# ABA-52563-SCH.net
KiCad netlist of a schematic drawn in Altium Designer
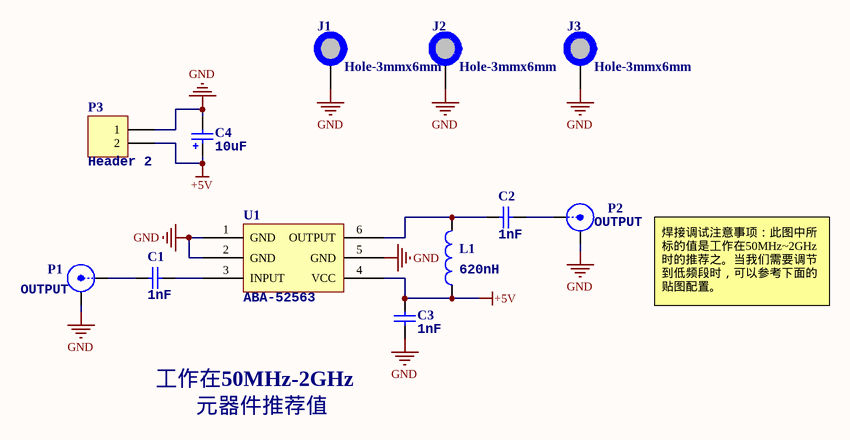
[diagram p0: ABA-52563-SCH.SchDoc]

(export (version "E")
  (design (tool "Eeschema 10.0.6"))
  (components
    (comp (ref "C1")
      (value "1nF")
      (footprint "0603C")
      (description "CAP CER 10000PF 100V X7R 0603")
      (fields
        (field (name "MANUFACTURER") "TDK Corporation")
        (field (name "MANUFACTURER PART NUMBER") "C1608X7R2A103K080AA")
      )
      (libsource (lib "Desiger_Schlib") (part "Cap1"))
    )
    (comp (ref "C2")
      (value "1nF")
      (footprint "0603C")
      (description "CAP CER 10000PF 100V X7R 0603")
      (fields
        (field (name "MANUFACTURER") "TDK Corporation")
        (field (name "MANUFACTURER PART NUMBER") "C1608X7R2A103K080AA")
      )
      (libsource (lib "Desiger_Schlib") (part "Cap1"))
    )
    (comp (ref "C3")
      (value "1nF")
      (footprint "0603C")
      (description "CAP CER 10000PF 100V X7R 0603")
      (fields
        (field (name "MANUFACTURER") "TDK Corporation")
        (field (name "MANUFACTURER PART NUMBER") "C1608X7R2A103K080AA")
      )
      (libsource (lib "Desiger_Schlib") (part "Cap1"))
    )
    (comp (ref "C4")
      (value "10uF")
      (footprint "1206T")
      (description "CAP TANT 10UF 10V 10% 1206")
      (fields
        (field (name "MANUFACTURER") "KEMET")
        (field (name "MANUFACTURER PART NUMBER") "T491A106K010AT7280")
      )
      (libsource (lib "Desiger_Schlib") (part "Cap2"))
    )
    (comp (ref "J1")
      (value "Hole-3mmx6mm")
      (footprint "Hole")
      (libsource (lib "Desiger_Schlib") (part "HOLED"))
    )
    (comp (ref "J2")
      (value "Hole-3mmx6mm")
      (footprint "Hole")
      (libsource (lib "Desiger_Schlib") (part "HOLED"))
    )
    (comp (ref "J3")
      (value "Hole-3mmx6mm")
      (footprint "Hole")
      (libsource (lib "Desiger_Schlib") (part "HOLED"))
    )
    (comp (ref "L1")
      (value "620nH")
      (footprint "0603L")
      (description "FIXED IND 240NH 4.4A 22MOHM SMD")
      (fields
        (field (name "MANUFACTURER") "Samsung Electro-Mechanics")
        (field (name "MANUFACTURER PART NUMBER") "CIGT201210UHR24MNE")
      )
      (libsource (lib "Desiger_Schlib") (part "Inductors"))
    )
    (comp (ref "P1")
      (value "OUTPUT")
      (footprint "SMA-SMD")
      (description "BNC Elbow Connector")
      (fields (field (name "PUBLISHER") "Altium Limited"))
      (libsource (lib "Miscellaneous Connectors") (part "BNC"))
    )
    (comp (ref "P2")
      (value "OUTPUT")
      (footprint "SMA-SMD")
      (description "BNC Elbow Connector")
      (fields (field (name "PUBLISHER") "Altium Limited"))
      (libsource (lib "Miscellaneous Connectors") (part "BNC"))
    )
    (comp (ref "P3")
      (value "Header 2")
      (footprint "KF2EDG_3R81_2P")
      (description "Header, 2-Pin")
      (fields (field (name "PUBLISHER") "Altium Limited"))
      (libsource (lib "Miscellaneous Connectors") (part "Header 2"))
    )
    (comp (ref "U1")
      (value "ABA-52563")
      (footprint "SOT23-6")
      (description "Agilent ABA-52563  3.5 GHz Broadband Silicon  RFIC Amplifier")
      (libsource (lib "Desiger_Schlib") (part "ABA-52563"))
    )
  )
  (nets
    (net (code "1") (name "+5V") (class "Default")
      (node (ref "C3") (pin "1") (pinfunction "1_1") (pintype "passive"))
      (node (ref "C4") (pin "1") (pinfunction "+_1") (pintype "passive"))
      (node (ref "L1") (pin "1") (pinfunction "1_1") (pintype "passive"))
      (node (ref "P3") (pin "2") (pinfunction "2_2") (pintype "passive"))
      (node (ref "U1") (pin "4") (pinfunction "VCC_4") (pintype "passive"))
    )
    (net (code "2") (name "GND") (class "Default")
      (node (ref "C3") (pin "2") (pinfunction "2_2") (pintype "passive"))
      (node (ref "C4") (pin "2") (pinfunction "-_2") (pintype "passive"))
      (node (ref "J1") (pin "0") (pinfunction "0_0") (pintype "passive"))
      (node (ref "J2") (pin "0") (pinfunction "0_0") (pintype "passive"))
      (node (ref "J3") (pin "0") (pinfunction "0_0") (pintype "passive"))
      (node (ref "P1") (pin "2") (pinfunction "Y_2") (pintype "passive"))
      (node (ref "P2") (pin "2") (pinfunction "Y_2") (pintype "passive"))
      (node (ref "P3") (pin "1") (pinfunction "1_1") (pintype "passive"))
      (node (ref "U1") (pin "1") (pinfunction "GND_1") (pintype "passive"))
      (node (ref "U1") (pin "2") (pinfunction "GND_2") (pintype "passive"))
      (node (ref "U1") (pin "5") (pinfunction "GND_5") (pintype "passive"))
    )
    (net (code "3") (name "Net-(P1-X)") (class "Default")
      (node (ref "C1") (pin "1") (pinfunction "1_1") (pintype "passive"))
      (node (ref "P1") (pin "1") (pinfunction "X_1") (pintype "passive"))
    )
    (net (code "4") (name "Net-(P2-X)") (class "Default")
      (node (ref "C2") (pin "2") (pinfunction "2_2") (pintype "passive"))
      (node (ref "P2") (pin "1") (pinfunction "X_1") (pintype "passive"))
    )
    (net (code "5") (name "Net-(U1-INPUT)") (class "Default")
      (node (ref "C1") (pin "2") (pinfunction "2_2") (pintype "passive"))
      (node (ref "U1") (pin "3") (pinfunction "INPUT_3") (pintype "passive"))
    )
    (net (code "6") (name "Net-(U1-OUTPUT)") (class "Default")
      (node (ref "C2") (pin "1") (pinfunction "1_1") (pintype "passive"))
      (node (ref "L1") (pin "2") (pinfunction "2_2") (pintype "passive"))
      (node (ref "U1") (pin "6") (pinfunction "OUTPUT_6") (pintype "passive"))
    )
  )
)
